# fram_rtc.net
KiCad netlist of a schematic drawn in Altium Designer
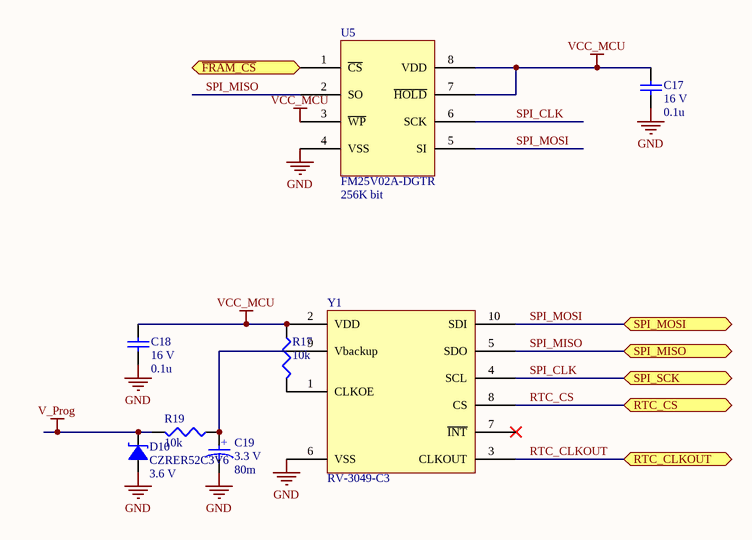
[diagram p0: fram_rtc.SchDoc]

(export (version "E")
  (design (tool "Eeschema 10.0.6"))
  (components
    (comp (ref "C17")
      (value "0.1u")
      (footprint "0402")
      (description "0.10µF ±10% 16V Ceramic Capacitor X7R 0402")
      (fields
        (field (name "VOLTAGE RATED") "16 V")
        (field (name "TOLERANCE") "10%")
        (field (name "MANUFACTURER PART NUMBER") "GRM155R71C104KA88D")
      )
      (libsource (lib "capacitors") (part "GRM155R71C104KA88D"))
    )
    (comp (ref "C18")
      (value "0.1u")
      (footprint "0402")
      (description "0.10µF ±10% 16V Ceramic Capacitor X7R 0402")
      (fields
        (field (name "VOLTAGE RATED") "16 V")
        (field (name "TOLERANCE") "10%")
        (field (name "MANUFACTURER PART NUMBER") "GRM155R71C104KA88D")
      )
      (libsource (lib "capacitors") (part "GRM155R71C104KA88D"))
    )
    (comp (ref "C19")
      (value "80m")
      (footprint "XH414HG-IV01E")
      (description "80mF (EDLC) Supercapacitor 3.3V Coin")
      (fields
        (field (name "VOLTAGE RATED") "3.3 V")
        (field (name "MANUFACTURER PART NUMBER") "XH414HG-IV01E")
      )
      (libsource (lib "capacitors") (part "XH414HG-IV01E"))
    )
    (comp (ref "D10")
      (value "CZRER52C3V6")
      (footprint "0503/SOD-723F")
      (description "Zener Diode 3.6V 150mW ±5% Surface Mount 0503 (1308 Metric)")
      (fields
        (field (name "MANUFACTURER") "Comchip Technology")
        (field (name "POWER") "150 mW")
        (field (name "ZENER VOLTAGE") "3.6 V")
      )
      (libsource (lib "diodes") (part "CZRER52C3V6"))
    )
    (comp (ref "R17")
      (value "10k")
      (footprint "0402")
      (description "RES SMD 10K OHM 1% 1/16W 0402")
      (fields (field (name "TOLERANCE") "1%") (field (name "POWER") "1/16 W"))
      (libsource (lib "resistors") (part "CRCW040210K0FKED"))
    )
    (comp (ref "R19")
      (value "10k")
      (footprint "0402")
      (description "RES SMD 10K OHM 1% 1/16W 0402")
      (fields (field (name "TOLERANCE") "1%") (field (name "POWER") "1/16 W"))
      (libsource (lib "resistors") (part "CRCW040210K0FKED"))
    )
    (comp (ref "U5")
      (value "FM25V02A-DGTR")
      (footprint "TDFN-8")
      (description "256-Kbit (32 K × 8) Serial (SPI) F-RAM")
      (fields (field (name "MANUFACTURER") "Cypress Semiconductor") (field (name "SIZE") "256K bit"))
      (libsource (lib "memory") (part "FM25V02A-DGTR"))
    )
    (comp (ref "Y1")
      (value "RV-3049-C3")
      (footprint "RV-3049-C3")
      (description "Real Time Clock Module with SPI-Bus")
      (libsource (lib "crystal oscillators") (part "RV-3049-C3"))
    )
  )
  (nets
    (net (code "1") (name "/RTC_CLKOUT") (class "Default")
      (node (ref "Y1") (pin "3") (pinfunction "CLKOUT_3") (pintype "passive"))
    )
    (net (code "2") (name "/RTC_CS") (class "Default")
      (node (ref "Y1") (pin "8") (pinfunction "CS_8") (pintype "passive"))
    )
    (net (code "3") (name "/SPI_CLK") (class "Default")
      (node (ref "U5") (pin "6") (pinfunction "SCK_6") (pintype "passive"))
      (node (ref "Y1") (pin "4") (pinfunction "SCL_4") (pintype "passive"))
    )
    (net (code "4") (name "/SPI_MISO") (class "Default")
      (node (ref "U5") (pin "2") (pinfunction "SO_2") (pintype "passive"))
      (node (ref "Y1") (pin "5") (pinfunction "SDO_5") (pintype "passive"))
    )
    (net (code "5") (name "/SPI_MOSI") (class "Default")
      (node (ref "U5") (pin "5") (pinfunction "SI_5") (pintype "passive"))
      (node (ref "Y1") (pin "10") (pinfunction "SDI_10") (pintype "passive"))
    )
    (net (code "6") (name "/~{FRAM_CS}") (class "Default")
      (node (ref "U5") (pin "1") (pinfunction "~{CS}_1") (pintype "passive"))
    )
    (net (code "7") (name "GND") (class "Default")
      (node (ref "C17") (pin "2") (pintype "passive"))
      (node (ref "C18") (pin "2") (pintype "passive"))
      (node (ref "C19") (pin "2") (pintype "passive"))
      (node (ref "D10") (pin "1") (pintype "passive"))
      (node (ref "U5") (pin "4") (pinfunction "VSS_4") (pintype "passive"))
      (node (ref "Y1") (pin "6") (pinfunction "VSS_6") (pintype "passive"))
    )
    (net (code "8") (name "Net-(Y1-CLKOE)") (class "Default")
      (node (ref "R17") (pin "1") (pintype "passive"))
      (node (ref "Y1") (pin "1") (pinfunction "CLKOE_1") (pintype "passive"))
    )
    (net (code "9") (name "Net-(Y1-Vbackup)") (class "Default")
      (node (ref "C19") (pin "1") (pintype "passive"))
      (node (ref "R19") (pin "2") (pintype "passive"))
      (node (ref "Y1") (pin "9") (pinfunction "Vbackup_9") (pintype "passive"))
    )
    (net (code "10") (name "VCC_MCU") (class "Default")
      (node (ref "C17") (pin "1") (pintype "passive"))
      (node (ref "C18") (pin "1") (pintype "passive"))
      (node (ref "R17") (pin "2") (pintype "passive"))
      (node (ref "U5") (pin "3") (pinfunction "~{WP}_3") (pintype "passive"))
      (node (ref "U5") (pin "7") (pinfunction "~{HOLD}_7") (pintype "passive"))
      (node (ref "U5") (pin "8") (pinfunction "VDD_8") (pintype "passive"))
      (node (ref "Y1") (pin "2") (pinfunction "VDD_2") (pintype "passive"))
    )
    (net (code "11") (name "V_Prog") (class "Default")
      (node (ref "D10") (pin "2") (pintype "passive"))
      (node (ref "R19") (pin "1") (pintype "passive"))
    )
    (net (code "12") (name "unconnected-(Y1-~{INT}-Pad7)") (class "Default")
      (node (ref "Y1") (pin "7") (pinfunction "~{INT}_7") (pintype "passive+no_connect"))
    )
  )
)
